# MK1.net
KiCad netlist of a schematic drawn in EAGLE
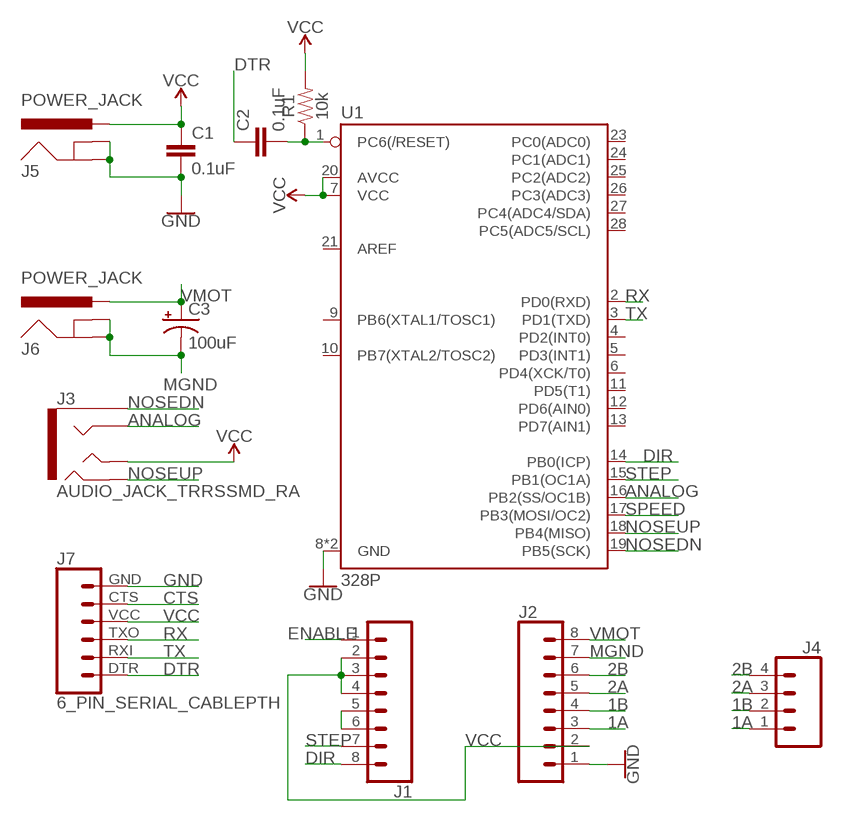
[diagram p0: schematic, sheet 1]

(export (version "E")
  (design (tool "Eeschema 10.0.6"))
  (components
    (comp (ref "C1")
      (value "0.1uF")
      (footprint "eagle-import:CAP-PTH-SMALL-KIT")
      (libsource (lib "eagle-import") (part "0.1UF-KIT-EZ-50V-20%"))
    )
    (comp (ref "C2")
      (value "0.1uF")
      (footprint "eagle-import:CAP-PTH-SMALL-KIT")
      (libsource (lib "eagle-import") (part "0.1UF-KIT-EZ-50V-20%"))
    )
    (comp (ref "C3")
      (value "100uF")
      (footprint "eagle-import:CPOL-RADIAL-2.5MM-6.5MM")
      (libsource (lib "eagle-import") (part "100UF-POLAR-RADIAL-2.5MM-25V-20%"))
    )
    (comp (ref "J1")
      (value "CONN_08\"")
      (footprint "eagle-import:1X08")
      (libsource (lib "eagle-import") (part "CONN_08{dblquote}"))
    )
    (comp (ref "J2")
      (value "CONN_08\"")
      (footprint "eagle-import:1X08")
      (libsource (lib "eagle-import") (part "CONN_08{dblquote}"))
    )
    (comp (ref "J3")
      (value "AUDIO_JACK_TRRSSMD_RA")
      (footprint "eagle-import:AUDIO_JACK_3.5MM_TRRS_SMD_RA")
      (libsource (lib "eagle-import") (part "AUDIO_JACK_TRRSSMD_RA"))
    )
    (comp (ref "J4")
      (value "CONN_04PTH")
      (footprint "eagle-import:1X04")
      (libsource (lib "eagle-import") (part "CONN_04PTH"))
    )
    (comp (ref "J5")
      (value "POWER_JACK")
      (footprint "eagle-import:POWER_JACK_PTH")
      (libsource (lib "eagle-import") (part "POWER_JACK"))
    )
    (comp (ref "J6")
      (value "POWER_JACK")
      (footprint "eagle-import:POWER_JACK_PTH")
      (libsource (lib "eagle-import") (part "POWER_JACK"))
    )
    (comp (ref "J7")
      (value "6_PIN_SERIAL_CABLEPTH")
      (footprint "eagle-import:FTDI_BASIC")
      (libsource (lib "eagle-import") (part "6_PIN_SERIAL_CABLEPTH"))
    )
    (comp (ref "R1")
      (value "10k")
      (footprint "eagle-import:AXIAL-0.3")
      (libsource (lib "eagle-import") (part "10KOHM-HORIZ-1/4W-1%"))
    )
    (comp (ref "U1")
      (value "328P")
      (footprint "eagle-import:DIP28")
      (libsource (lib "eagle-import") (part "ATMEGA328P_PDIP"))
    )
  )
  (nets
    (net (code "1") (name "1A") (class "Default")
      (node (ref "J2") (pin "3") (pinfunction "3_3") (pintype "passive"))
      (node (ref "J4") (pin "1") (pinfunction "1_1") (pintype "passive"))
    )
    (net (code "2") (name "1B") (class "Default")
      (node (ref "J2") (pin "4") (pinfunction "4_4") (pintype "passive"))
      (node (ref "J4") (pin "2") (pinfunction "2_2") (pintype "passive"))
    )
    (net (code "3") (name "2A") (class "Default")
      (node (ref "J2") (pin "5") (pinfunction "5_5") (pintype "passive"))
      (node (ref "J4") (pin "3") (pinfunction "3_3") (pintype "passive"))
    )
    (net (code "4") (name "2B") (class "Default")
      (node (ref "J2") (pin "6") (pinfunction "6_6") (pintype "passive"))
      (node (ref "J4") (pin "4") (pinfunction "4_4") (pintype "passive"))
    )
    (net (code "5") (name "ANALOG") (class "Default")
      (node (ref "J3") (pin "RING1") (pinfunction "RING1_RING1") (pintype "bidirectional"))
      (node (ref "U1") (pin "16") (pinfunction "PB2(SS/OC1B)_16") (pintype "bidirectional"))
    )
    (net (code "6") (name "CTS") (class "Default")
      (node (ref "J7") (pin "CTS") (pinfunction "5_CTS") (pintype "passive"))
    )
    (net (code "7") (name "DIR") (class "Default")
      (node (ref "J1") (pin "8") (pinfunction "8_8") (pintype "passive"))
      (node (ref "U1") (pin "14") (pinfunction "PB0(ICP)_14") (pintype "bidirectional"))
    )
    (net (code "8") (name "DTR") (class "Default")
      (node (ref "C2") (pin "1") (pinfunction "1_1") (pintype "passive"))
      (node (ref "J7") (pin "DTR") (pinfunction "1_DTR") (pintype "passive"))
    )
    (net (code "9") (name "ENABLE") (class "Default")
      (node (ref "J1") (pin "1") (pinfunction "1_1") (pintype "passive"))
    )
    (net (code "10") (name "GND") (class "Default")
      (node (ref "C1") (pin "2") (pinfunction "2_2") (pintype "passive"))
      (node (ref "J2") (pin "1") (pinfunction "1_1") (pintype "passive"))
      (node (ref "J5") (pin "GND") (pinfunction "GND_GND") (pintype "bidirectional"))
      (node (ref "J5") (pin "GNDBREAK") (pinfunction "GNDBREAK_GNDBREAK") (pintype "bidirectional"))
      (node (ref "J7") (pin "GND") (pinfunction "6_GND") (pintype "passive"))
      (node (ref "U1") (pin "22") (pinfunction "GND_22") (pintype "bidirectional"))
      (node (ref "U1") (pin "8") (pinfunction "GND_8") (pintype "bidirectional"))
    )
    (net (code "11") (name "MGND") (class "Default")
      (node (ref "C3") (pin "2") (pinfunction "-_2") (pintype "passive"))
      (node (ref "J2") (pin "7") (pinfunction "7_7") (pintype "passive"))
      (node (ref "J6") (pin "GND") (pinfunction "GND_GND") (pintype "bidirectional"))
      (node (ref "J6") (pin "GNDBREAK") (pinfunction "GNDBREAK_GNDBREAK") (pintype "bidirectional"))
    )
    (net (code "12") (name "NOSEDN") (class "Default")
      (node (ref "J3") (pin "EARTH") (pinfunction "EARTH_EARTH") (pintype "bidirectional"))
      (node (ref "U1") (pin "19") (pinfunction "PB5(SCK)_19") (pintype "bidirectional"))
    )
    (net (code "13") (name "NOSEUP") (class "Default")
      (node (ref "J3") (pin "RING2") (pinfunction "RING2_RING2") (pintype "bidirectional"))
      (node (ref "U1") (pin "18") (pinfunction "PB4(MISO)_18") (pintype "bidirectional"))
    )
    (net (code "14") (name "Net-(J1-Pad5)") (class "Default")
      (node (ref "J1") (pin "5") (pinfunction "5_5") (pintype "passive"))
      (node (ref "J1") (pin "6") (pinfunction "6_6") (pintype "passive"))
    )
    (net (code "15") (name "Net-(R1-1)") (class "Default")
      (node (ref "C2") (pin "2") (pinfunction "2_2") (pintype "passive"))
      (node (ref "R1") (pin "P$1") (pinfunction "1_P$1") (pintype "passive"))
      (node (ref "U1") (pin "1") (pinfunction "PC6(/RESET)_1") (pintype "bidirectional"))
    )
    (net (code "16") (name "RX") (class "Default")
      (node (ref "J7") (pin "TXO") (pinfunction "3_TXO") (pintype "passive"))
      (node (ref "U1") (pin "2") (pinfunction "PD0(RXD)_2") (pintype "bidirectional"))
    )
    (net (code "17") (name "SPEED") (class "Default")
      (node (ref "U1") (pin "17") (pinfunction "PB3(MOSI/OC2)_17") (pintype "bidirectional"))
    )
    (net (code "18") (name "STEP") (class "Default")
      (node (ref "J1") (pin "7") (pinfunction "7_7") (pintype "passive"))
      (node (ref "U1") (pin "15") (pinfunction "PB1(OC1A)_15") (pintype "bidirectional"))
    )
    (net (code "19") (name "TX") (class "Default")
      (node (ref "J7") (pin "RXI") (pinfunction "2_RXI") (pintype "passive"))
      (node (ref "U1") (pin "3") (pinfunction "PD1(TXD)_3") (pintype "bidirectional"))
    )
    (net (code "20") (name "VCC") (class "Default")
      (node (ref "C1") (pin "1") (pinfunction "1_1") (pintype "passive"))
      (node (ref "J1") (pin "2") (pinfunction "2_2") (pintype "passive"))
      (node (ref "J1") (pin "3") (pinfunction "3_3") (pintype "passive"))
      (node (ref "J1") (pin "4") (pinfunction "4_4") (pintype "passive"))
      (node (ref "J2") (pin "2") (pinfunction "2_2") (pintype "passive"))
      (node (ref "J3") (pin "TIP") (pinfunction "TIP_TIP") (pintype "bidirectional"))
      (node (ref "J5") (pin "PWR") (pinfunction "PWR_PWR") (pintype "bidirectional"))
      (node (ref "J7") (pin "VCC") (pinfunction "4_VCC") (pintype "passive"))
      (node (ref "R1") (pin "P$2") (pinfunction "2_P$2") (pintype "passive"))
      (node (ref "U1") (pin "20") (pinfunction "AVCC_20") (pintype "bidirectional"))
      (node (ref "U1") (pin "7") (pinfunction "VCC_7") (pintype "bidirectional"))
    )
    (net (code "21") (name "VMOT") (class "Default")
      (node (ref "C3") (pin "1") (pinfunction "+_1") (pintype "passive"))
      (node (ref "J2") (pin "8") (pinfunction "8_8") (pintype "passive"))
      (node (ref "J6") (pin "PWR") (pinfunction "PWR_PWR") (pintype "bidirectional"))
    )
    (net (code "22") (name "unconnected-(U1-AREF-Pad21)") (class "Default")
      (node (ref "U1") (pin "21") (pinfunction "AREF_21") (pintype "bidirectional"))
    )
    (net (code "23") (name "unconnected-(U1-PB6(XTAL1{slash}TOSC1)-Pad9)") (class "Default")
      (node (ref "U1") (pin "9") (pinfunction "PB6(XTAL1/TOSC1)_9") (pintype "bidirectional"))
    )
    (net (code "24") (name "unconnected-(U1-PB7(XTAL2{slash}TOSC2)-Pad10)") (class "Default")
      (node (ref "U1") (pin "10") (pinfunction "PB7(XTAL2/TOSC2)_10") (pintype "bidirectional"))
    )
    (net (code "25") (name "unconnected-(U1-PC0(ADC0)-Pad23)") (class "Default")
      (node (ref "U1") (pin "23") (pinfunction "PC0(ADC0)_23") (pintype "bidirectional"))
    )
    (net (code "26") (name "unconnected-(U1-PC1(ADC1)-Pad24)") (class "Default")
      (node (ref "U1") (pin "24") (pinfunction "PC1(ADC1)_24") (pintype "bidirectional"))
    )
    (net (code "27") (name "unconnected-(U1-PC2(ADC2)-Pad25)") (class "Default")
      (node (ref "U1") (pin "25") (pinfunction "PC2(ADC2)_25") (pintype "bidirectional"))
    )
    (net (code "28") (name "unconnected-(U1-PC3(ADC3)-Pad26)") (class "Default")
      (node (ref "U1") (pin "26") (pinfunction "PC3(ADC3)_26") (pintype "bidirectional"))
    )
    (net (code "29") (name "unconnected-(U1-PC4(ADC4{slash}SDA)-Pad27)") (class "Default")
      (node (ref "U1") (pin "27") (pinfunction "PC4(ADC4/SDA)_27") (pintype "bidirectional"))
    )
    (net (code "30") (name "unconnected-(U1-PC5(ADC5{slash}SCL)-Pad28)") (class "Default")
      (node (ref "U1") (pin "28") (pinfunction "PC5(ADC5/SCL)_28") (pintype "bidirectional"))
    )
    (net (code "31") (name "unconnected-(U1-PD2(INT0)-Pad4)") (class "Default")
      (node (ref "U1") (pin "4") (pinfunction "PD2(INT0)_4") (pintype "bidirectional"))
    )
    (net (code "32") (name "unconnected-(U1-PD3(INT1)-Pad5)") (class "Default")
      (node (ref "U1") (pin "5") (pinfunction "PD3(INT1)_5") (pintype "bidirectional"))
    )
    (net (code "33") (name "unconnected-(U1-PD4(XCK{slash}T0)-Pad6)") (class "Default")
      (node (ref "U1") (pin "6") (pinfunction "PD4(XCK/T0)_6") (pintype "bidirectional"))
    )
    (net (code "34") (name "unconnected-(U1-PD5(T1)-Pad11)") (class "Default")
      (node (ref "U1") (pin "11") (pinfunction "PD5(T1)_11") (pintype "bidirectional"))
    )
    (net (code "35") (name "unconnected-(U1-PD6(AIN0)-Pad12)") (class "Default")
      (node (ref "U1") (pin "12") (pinfunction "PD6(AIN0)_12") (pintype "bidirectional"))
    )
    (net (code "36") (name "unconnected-(U1-PD7(AIN1)-Pad13)") (class "Default")
      (node (ref "U1") (pin "13") (pinfunction "PD7(AIN1)_13") (pintype "bidirectional"))
    )
  )
)
